# DDR3L.net
KiCad netlist of a schematic drawn in Altium Designer
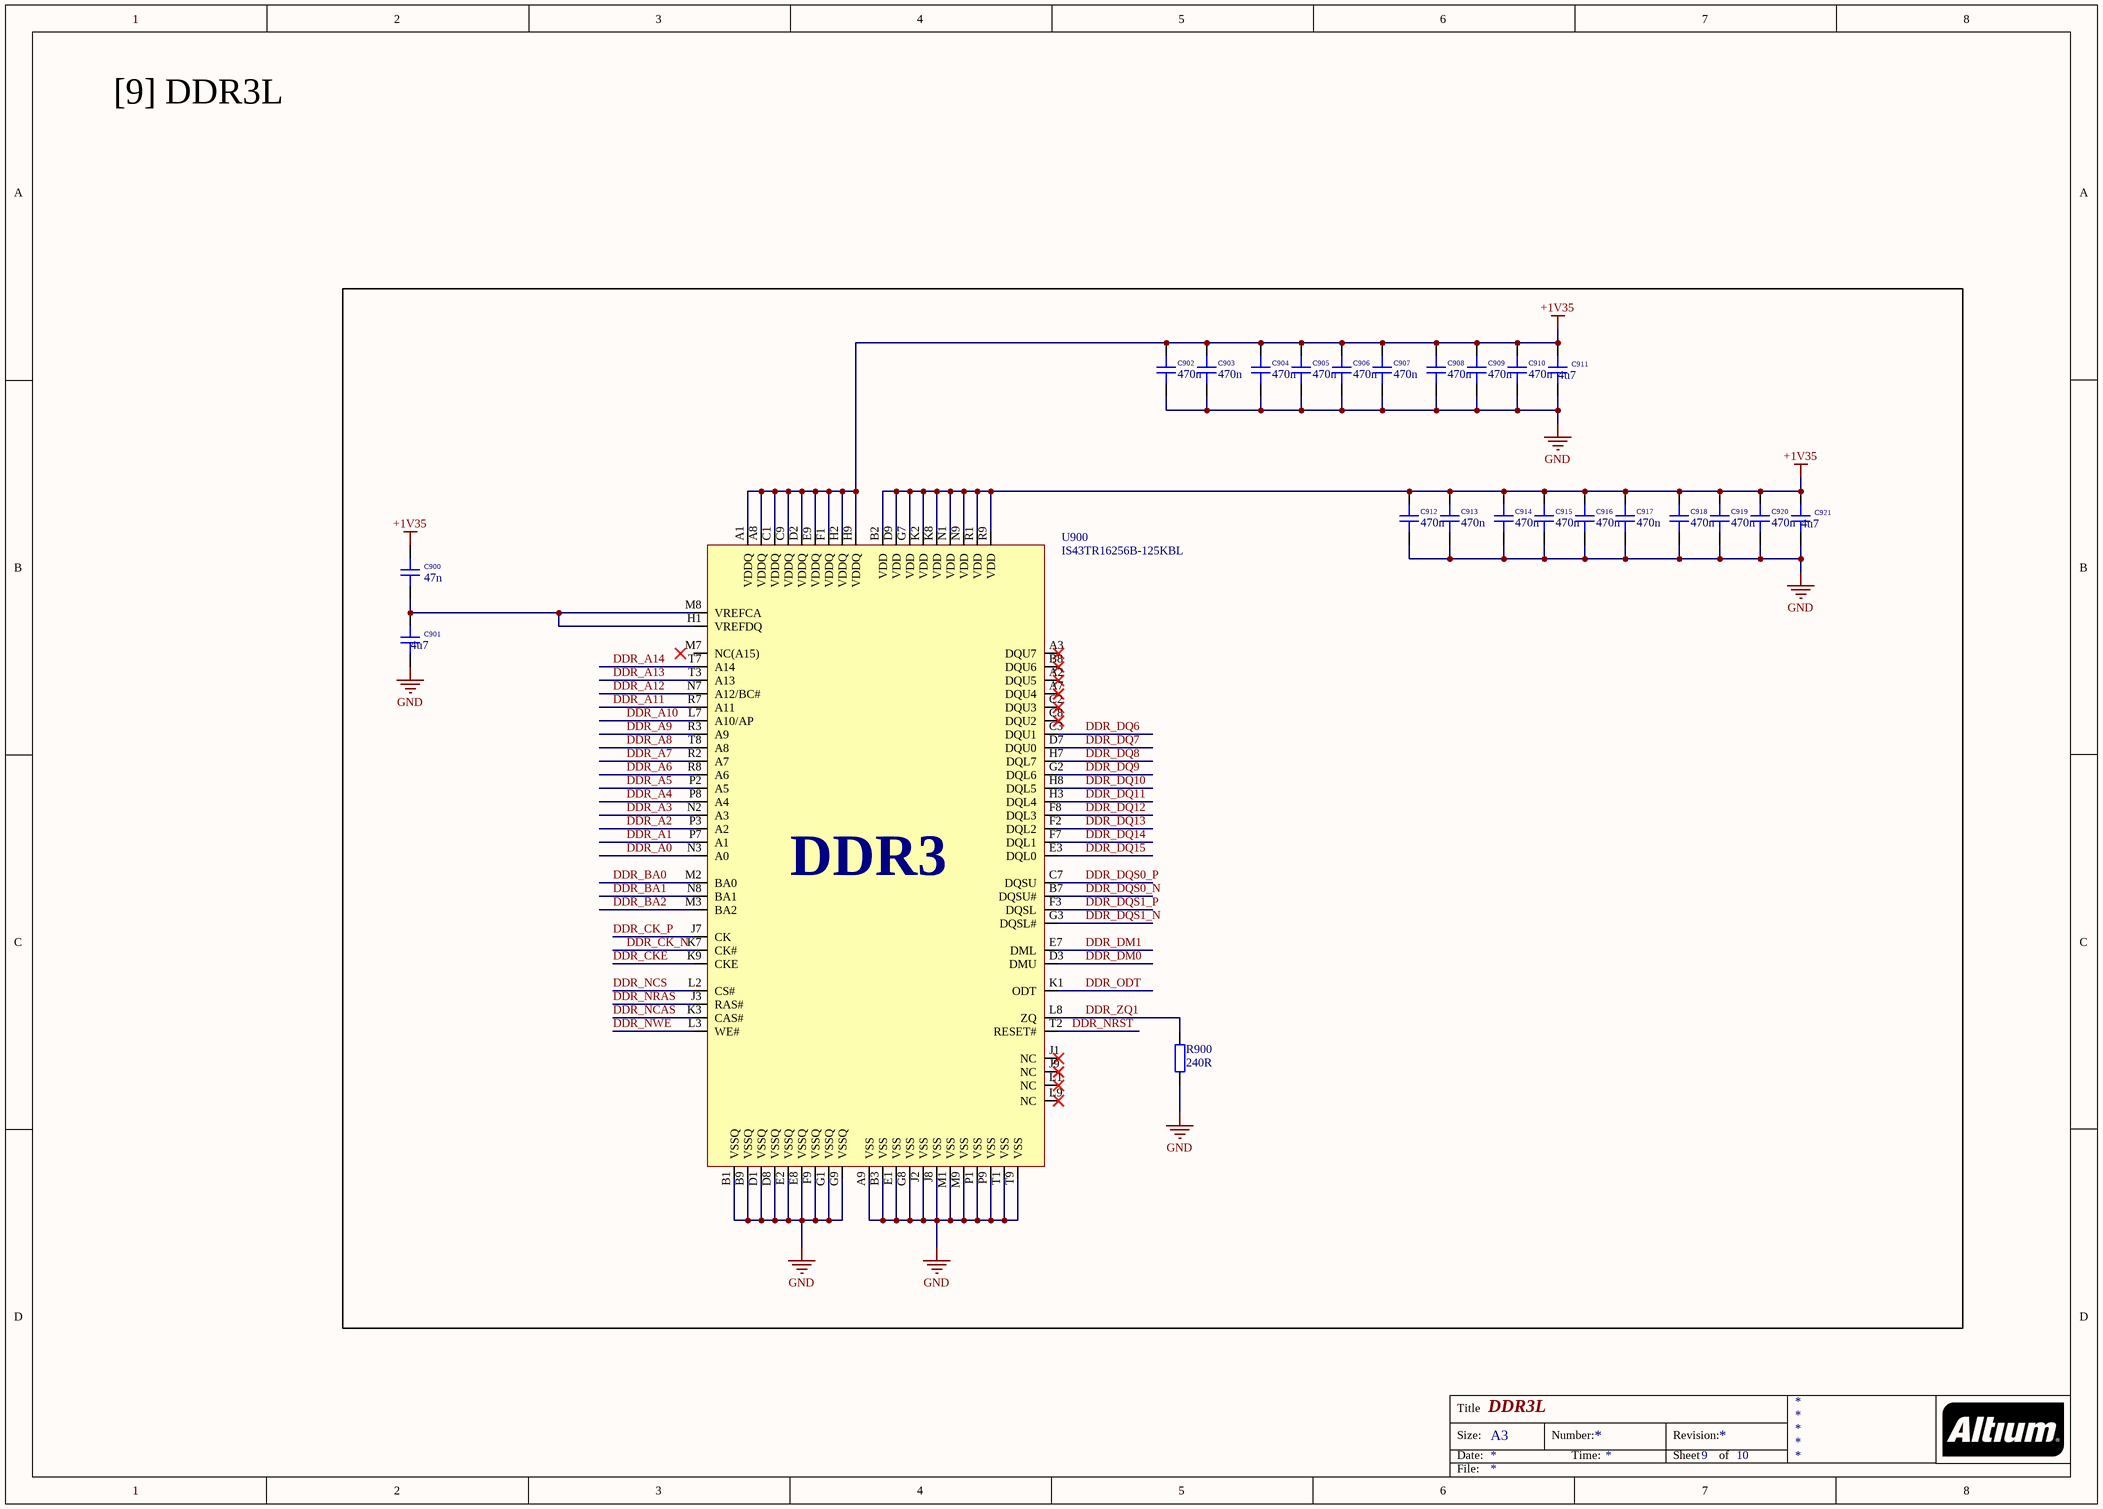
[diagram p0: DDR3L.SchDoc]

(export (version "E")
  (design (tool "Eeschema 10.0.6"))
  (components
    (comp (ref "C900")
      (value "47n")
      (footprint "CAP_1210")
      (description "Capacitor SMD 1210")
      (libsource (lib "Schematic-Lib-PhilsLab") (part "CAP_1210"))
    )
    (comp (ref "C901")
      (value "4u7")
      (footprint "CAP_1210")
      (description "Capacitor SMD 1210")
      (libsource (lib "Schematic-Lib-PhilsLab") (part "CAP_1210"))
    )
    (comp (ref "C902")
      (value "470n")
      (footprint "CAP_1210")
      (description "Capacitor SMD 1210")
      (libsource (lib "Schematic-Lib-PhilsLab") (part "CAP_1210"))
    )
    (comp (ref "C903")
      (value "470n")
      (footprint "CAP_1210")
      (description "Capacitor SMD 1210")
      (libsource (lib "Schematic-Lib-PhilsLab") (part "CAP_1210"))
    )
    (comp (ref "C904")
      (value "470n")
      (footprint "CAP_1210")
      (description "Capacitor SMD 1210")
      (libsource (lib "Schematic-Lib-PhilsLab") (part "CAP_1210"))
    )
    (comp (ref "C905")
      (value "470n")
      (footprint "CAP_1210")
      (description "Capacitor SMD 1210")
      (libsource (lib "Schematic-Lib-PhilsLab") (part "CAP_1210"))
    )
    (comp (ref "C906")
      (value "470n")
      (footprint "CAP_1210")
      (description "Capacitor SMD 1210")
      (libsource (lib "Schematic-Lib-PhilsLab") (part "CAP_1210"))
    )
    (comp (ref "C907")
      (value "470n")
      (footprint "CAP_1210")
      (description "Capacitor SMD 1210")
      (libsource (lib "Schematic-Lib-PhilsLab") (part "CAP_1210"))
    )
    (comp (ref "C908")
      (value "470n")
      (footprint "CAP_1210")
      (description "Capacitor SMD 1210")
      (libsource (lib "Schematic-Lib-PhilsLab") (part "CAP_1210"))
    )
    (comp (ref "C909")
      (value "470n")
      (footprint "CAP_1210")
      (description "Capacitor SMD 1210")
      (libsource (lib "Schematic-Lib-PhilsLab") (part "CAP_1210"))
    )
    (comp (ref "C910")
      (value "470n")
      (footprint "CAP_1210")
      (description "Capacitor SMD 1210")
      (libsource (lib "Schematic-Lib-PhilsLab") (part "CAP_1210"))
    )
    (comp (ref "C911")
      (value "4u7")
      (footprint "CAP_1210")
      (description "Capacitor SMD 1210")
      (libsource (lib "Schematic-Lib-PhilsLab") (part "CAP_1210"))
    )
    (comp (ref "C912")
      (value "470n")
      (footprint "CAP_1210")
      (description "Capacitor SMD 1210")
      (libsource (lib "Schematic-Lib-PhilsLab") (part "CAP_1210"))
    )
    (comp (ref "C913")
      (value "470n")
      (footprint "CAP_1210")
      (description "Capacitor SMD 1210")
      (libsource (lib "Schematic-Lib-PhilsLab") (part "CAP_1210"))
    )
    (comp (ref "C914")
      (value "470n")
      (footprint "CAP_1210")
      (description "Capacitor SMD 1210")
      (libsource (lib "Schematic-Lib-PhilsLab") (part "CAP_1210"))
    )
    (comp (ref "C915")
      (value "470n")
      (footprint "CAP_1210")
      (description "Capacitor SMD 1210")
      (libsource (lib "Schematic-Lib-PhilsLab") (part "CAP_1210"))
    )
    (comp (ref "C916")
      (value "470n")
      (footprint "CAP_1210")
      (description "Capacitor SMD 1210")
      (libsource (lib "Schematic-Lib-PhilsLab") (part "CAP_1210"))
    )
    (comp (ref "C917")
      (value "470n")
      (footprint "CAP_1210")
      (description "Capacitor SMD 1210")
      (libsource (lib "Schematic-Lib-PhilsLab") (part "CAP_1210"))
    )
    (comp (ref "C918")
      (value "470n")
      (footprint "CAP_1210")
      (description "Capacitor SMD 1210")
      (libsource (lib "Schematic-Lib-PhilsLab") (part "CAP_1210"))
    )
    (comp (ref "C919")
      (value "470n")
      (footprint "CAP_1210")
      (description "Capacitor SMD 1210")
      (libsource (lib "Schematic-Lib-PhilsLab") (part "CAP_1210"))
    )
    (comp (ref "C920")
      (value "470n")
      (footprint "CAP_1210")
      (description "Capacitor SMD 1210")
      (libsource (lib "Schematic-Lib-PhilsLab") (part "CAP_1210"))
    )
    (comp (ref "C921")
      (value "4u7")
      (footprint "CAP_1210")
      (description "Capacitor SMD 1210")
      (libsource (lib "Schematic-Lib-PhilsLab") (part "CAP_1210"))
    )
    (comp (ref "R900")
      (value "240R")
      (footprint "RES_0402")
      (description "Resistor SMD 0402")
      (libsource (lib "Schematic-Lib-PhilsLab") (part "RES_0402"))
    )
    (comp (ref "U900")
      (value "IS43TR16256B-125KBL")
      (footprint "BGA96C80P9X16_900X1300X120")
      (description "DRAM 4GBit, 1.5V, DDR3, 256Mx16, 1600MT/s @ 11-11-11, 96 ball BGA (9mm x13mm) RoHS")
      (fields (field (name "MANUFACTURER") "ISSI"))
      (libsource (lib "Schematic-Lib-PhilsLab") (part "IS43TR16256B-125KBL"))
    )
  )
  (nets
    (net (code "1") (name "+1V35") (class "Default")
      (node (ref "C900") (pin "2") (pinfunction "2_2") (pintype "passive"))
      (node (ref "C902") (pin "2") (pinfunction "2_2") (pintype "passive"))
      (node (ref "C903") (pin "2") (pinfunction "2_2") (pintype "passive"))
      (node (ref "C904") (pin "2") (pinfunction "2_2") (pintype "passive"))
      (node (ref "C905") (pin "2") (pinfunction "2_2") (pintype "passive"))
      (node (ref "C906") (pin "2") (pinfunction "2_2") (pintype "passive"))
      (node (ref "C907") (pin "2") (pinfunction "2_2") (pintype "passive"))
      (node (ref "C908") (pin "2") (pinfunction "2_2") (pintype "passive"))
      (node (ref "C909") (pin "2") (pinfunction "2_2") (pintype "passive"))
      (node (ref "C910") (pin "2") (pinfunction "2_2") (pintype "passive"))
      (node (ref "C911") (pin "2") (pinfunction "2_2") (pintype "passive"))
      (node (ref "C912") (pin "2") (pinfunction "2_2") (pintype "passive"))
      (node (ref "C913") (pin "2") (pinfunction "2_2") (pintype "passive"))
      (node (ref "C914") (pin "2") (pinfunction "2_2") (pintype "passive"))
      (node (ref "C915") (pin "2") (pinfunction "2_2") (pintype "passive"))
      (node (ref "C916") (pin "2") (pinfunction "2_2") (pintype "passive"))
      (node (ref "C917") (pin "2") (pinfunction "2_2") (pintype "passive"))
      (node (ref "C918") (pin "2") (pinfunction "2_2") (pintype "passive"))
      (node (ref "C919") (pin "2") (pinfunction "2_2") (pintype "passive"))
      (node (ref "C920") (pin "2") (pinfunction "2_2") (pintype "passive"))
      (node (ref "C921") (pin "2") (pinfunction "2_2") (pintype "passive"))
      (node (ref "U900") (pin "A1") (pinfunction "VDDQ_A1") (pintype "passive"))
      (node (ref "U900") (pin "A8") (pinfunction "VDDQ_A8") (pintype "passive"))
      (node (ref "U900") (pin "B2") (pinfunction "VDD_B2") (pintype "passive"))
      (node (ref "U900") (pin "C1") (pinfunction "VDDQ_C1") (pintype "passive"))
      (node (ref "U900") (pin "C9") (pinfunction "VDDQ_C9") (pintype "passive"))
      (node (ref "U900") (pin "D2") (pinfunction "VDDQ_D2") (pintype "passive"))
      (node (ref "U900") (pin "D9") (pinfunction "VDD_D9") (pintype "passive"))
      (node (ref "U900") (pin "E9") (pinfunction "VDDQ_E9") (pintype "passive"))
      (node (ref "U900") (pin "F1") (pinfunction "VDDQ_F1") (pintype "passive"))
      (node (ref "U900") (pin "G7") (pinfunction "VDD_G7") (pintype "passive"))
      (node (ref "U900") (pin "H2") (pinfunction "VDDQ_H2") (pintype "passive"))
      (node (ref "U900") (pin "H9") (pinfunction "VDDQ_H9") (pintype "passive"))
      (node (ref "U900") (pin "K2") (pinfunction "VDD_K2") (pintype "passive"))
      (node (ref "U900") (pin "K8") (pinfunction "VDD_K8") (pintype "passive"))
      (node (ref "U900") (pin "N1") (pinfunction "VDD_N1") (pintype "passive"))
      (node (ref "U900") (pin "N9") (pinfunction "VDD_N9") (pintype "passive"))
      (node (ref "U900") (pin "R1") (pinfunction "VDD_R1") (pintype "passive"))
      (node (ref "U900") (pin "R9") (pinfunction "VDD_R9") (pintype "passive"))
    )
    (net (code "2") (name "/DDR_A0") (class "Default")
      (node (ref "U900") (pin "N3") (pinfunction "A0_N3") (pintype "passive"))
    )
    (net (code "3") (name "/DDR_A1") (class "Default")
      (node (ref "U900") (pin "P7") (pinfunction "A1_P7") (pintype "passive"))
    )
    (net (code "4") (name "/DDR_A2") (class "Default")
      (node (ref "U900") (pin "P3") (pinfunction "A2_P3") (pintype "passive"))
    )
    (net (code "5") (name "/DDR_A3") (class "Default")
      (node (ref "U900") (pin "N2") (pinfunction "A3_N2") (pintype "passive"))
    )
    (net (code "6") (name "/DDR_A4") (class "Default")
      (node (ref "U900") (pin "P8") (pinfunction "A4_P8") (pintype "passive"))
    )
    (net (code "7") (name "/DDR_A5") (class "Default")
      (node (ref "U900") (pin "P2") (pinfunction "A5_P2") (pintype "passive"))
    )
    (net (code "8") (name "/DDR_A6") (class "Default")
      (node (ref "U900") (pin "R8") (pinfunction "A6_R8") (pintype "passive"))
    )
    (net (code "9") (name "/DDR_A7") (class "Default")
      (node (ref "U900") (pin "R2") (pinfunction "A7_R2") (pintype "passive"))
    )
    (net (code "10") (name "/DDR_A8") (class "Default")
      (node (ref "U900") (pin "T8") (pinfunction "A8_T8") (pintype "passive"))
    )
    (net (code "11") (name "/DDR_A9") (class "Default")
      (node (ref "U900") (pin "R3") (pinfunction "A9_R3") (pintype "passive"))
    )
    (net (code "12") (name "/DDR_A10") (class "Default")
      (node (ref "U900") (pin "L7") (pinfunction "A10/AP_L7") (pintype "passive"))
    )
    (net (code "13") (name "/DDR_A11") (class "Default")
      (node (ref "U900") (pin "R7") (pinfunction "A11_R7") (pintype "passive"))
    )
    (net (code "14") (name "/DDR_A12") (class "Default")
      (node (ref "U900") (pin "N7") (pinfunction "A12/BC#_N7") (pintype "passive"))
    )
    (net (code "15") (name "/DDR_A13") (class "Default")
      (node (ref "U900") (pin "T3") (pinfunction "A13_T3") (pintype "passive"))
    )
    (net (code "16") (name "/DDR_A14") (class "Default")
      (node (ref "U900") (pin "T7") (pinfunction "A14_T7") (pintype "passive"))
    )
    (net (code "17") (name "/DDR_BA0") (class "Default")
      (node (ref "U900") (pin "M2") (pinfunction "BA0_M2") (pintype "passive"))
    )
    (net (code "18") (name "/DDR_BA1") (class "Default")
      (node (ref "U900") (pin "N8") (pinfunction "BA1_N8") (pintype "passive"))
    )
    (net (code "19") (name "/DDR_BA2") (class "Default")
      (node (ref "U900") (pin "M3") (pinfunction "BA2_M3") (pintype "passive"))
    )
    (net (code "20") (name "/DDR_CKE") (class "Default")
      (node (ref "U900") (pin "K9") (pinfunction "CKE_K9") (pintype "passive"))
    )
    (net (code "21") (name "/DDR_CK_N") (class "Default")
      (node (ref "U900") (pin "K7") (pinfunction "CK#_K7") (pintype "passive"))
    )
    (net (code "22") (name "/DDR_CK_P") (class "Default")
      (node (ref "U900") (pin "J7") (pinfunction "CK_J7") (pintype "passive"))
    )
    (net (code "23") (name "/DDR_DM0") (class "Default")
      (node (ref "U900") (pin "D3") (pinfunction "DMU_D3") (pintype "passive"))
    )
    (net (code "24") (name "/DDR_DM1") (class "Default")
      (node (ref "U900") (pin "E7") (pinfunction "DML_E7") (pintype "passive"))
    )
    (net (code "25") (name "/DDR_DQ6") (class "Default")
      (node (ref "U900") (pin "C3") (pinfunction "DQU1_C3") (pintype "passive"))
    )
    (net (code "26") (name "/DDR_DQ7") (class "Default")
      (node (ref "U900") (pin "D7") (pinfunction "DQU0_D7") (pintype "passive"))
    )
    (net (code "27") (name "/DDR_DQ8") (class "Default")
      (node (ref "U900") (pin "H7") (pinfunction "DQL7_H7") (pintype "passive"))
    )
    (net (code "28") (name "/DDR_DQ9") (class "Default")
      (node (ref "U900") (pin "G2") (pinfunction "DQL6_G2") (pintype "passive"))
    )
    (net (code "29") (name "/DDR_DQ10") (class "Default")
      (node (ref "U900") (pin "H8") (pinfunction "DQL5_H8") (pintype "passive"))
    )
    (net (code "30") (name "/DDR_DQ11") (class "Default")
      (node (ref "U900") (pin "H3") (pinfunction "DQL4_H3") (pintype "passive"))
    )
    (net (code "31") (name "/DDR_DQ12") (class "Default")
      (node (ref "U900") (pin "F8") (pinfunction "DQL3_F8") (pintype "passive"))
    )
    (net (code "32") (name "/DDR_DQ13") (class "Default")
      (node (ref "U900") (pin "F2") (pinfunction "DQL2_F2") (pintype "passive"))
    )
    (net (code "33") (name "/DDR_DQ14") (class "Default")
      (node (ref "U900") (pin "F7") (pinfunction "DQL1_F7") (pintype "passive"))
    )
    (net (code "34") (name "/DDR_DQ15") (class "Default")
      (node (ref "U900") (pin "E3") (pinfunction "DQL0_E3") (pintype "passive"))
    )
    (net (code "35") (name "/DDR_DQS0_N") (class "Default")
      (node (ref "U900") (pin "B7") (pinfunction "DQSU#_B7") (pintype "passive"))
    )
    (net (code "36") (name "/DDR_DQS0_P") (class "Default")
      (node (ref "U900") (pin "C7") (pinfunction "DQSU_C7") (pintype "passive"))
    )
    (net (code "37") (name "/DDR_DQS1_N") (class "Default")
      (node (ref "U900") (pin "G3") (pinfunction "DQSL#_G3") (pintype "passive"))
    )
    (net (code "38") (name "/DDR_DQS1_P") (class "Default")
      (node (ref "U900") (pin "F3") (pinfunction "DQSL_F3") (pintype "passive"))
    )
    (net (code "39") (name "/DDR_NCAS") (class "Default")
      (node (ref "U900") (pin "K3") (pinfunction "CAS#_K3") (pintype "passive"))
    )
    (net (code "40") (name "/DDR_NCS") (class "Default")
      (node (ref "U900") (pin "L2") (pinfunction "CS#_L2") (pintype "passive"))
    )
    (net (code "41") (name "/DDR_NRAS") (class "Default")
      (node (ref "U900") (pin "J3") (pinfunction "RAS#_J3") (pintype "passive"))
    )
    (net (code "42") (name "/DDR_NRST") (class "Default")
      (node (ref "U900") (pin "T2") (pinfunction "RESET#_T2") (pintype "passive"))
    )
    (net (code "43") (name "/DDR_NWE") (class "Default")
      (node (ref "U900") (pin "L3") (pinfunction "WE#_L3") (pintype "passive"))
    )
    (net (code "44") (name "/DDR_ODT") (class "Default")
      (node (ref "U900") (pin "K1") (pinfunction "ODT_K1") (pintype "passive"))
    )
    (net (code "45") (name "/DDR_ZQ1") (class "Default")
      (node (ref "R900") (pin "1") (pinfunction "1_1") (pintype "passive"))
      (node (ref "U900") (pin "L8") (pinfunction "ZQ_L8") (pintype "passive"))
    )
    (net (code "46") (name "GND") (class "Default")
      (node (ref "C901") (pin "1") (pinfunction "1_1") (pintype "passive"))
      (node (ref "C902") (pin "1") (pinfunction "1_1") (pintype "passive"))
      (node (ref "C903") (pin "1") (pinfunction "1_1") (pintype "passive"))
      (node (ref "C904") (pin "1") (pinfunction "1_1") (pintype "passive"))
      (node (ref "C905") (pin "1") (pinfunction "1_1") (pintype "passive"))
      (node (ref "C906") (pin "1") (pinfunction "1_1") (pintype "passive"))
      (node (ref "C907") (pin "1") (pinfunction "1_1") (pintype "passive"))
      (node (ref "C908") (pin "1") (pinfunction "1_1") (pintype "passive"))
      (node (ref "C909") (pin "1") (pinfunction "1_1") (pintype "passive"))
      (node (ref "C910") (pin "1") (pinfunction "1_1") (pintype "passive"))
      (node (ref "C911") (pin "1") (pinfunction "1_1") (pintype "passive"))
      (node (ref "C912") (pin "1") (pinfunction "1_1") (pintype "passive"))
      (node (ref "C913") (pin "1") (pinfunction "1_1") (pintype "passive"))
      (node (ref "C914") (pin "1") (pinfunction "1_1") (pintype "passive"))
      (node (ref "C915") (pin "1") (pinfunction "1_1") (pintype "passive"))
      (node (ref "C916") (pin "1") (pinfunction "1_1") (pintype "passive"))
      (node (ref "C917") (pin "1") (pinfunction "1_1") (pintype "passive"))
      (node (ref "C918") (pin "1") (pinfunction "1_1") (pintype "passive"))
      (node (ref "C919") (pin "1") (pinfunction "1_1") (pintype "passive"))
      (node (ref "C920") (pin "1") (pinfunction "1_1") (pintype "passive"))
      (node (ref "C921") (pin "1") (pinfunction "1_1") (pintype "passive"))
      (node (ref "R900") (pin "2") (pinfunction "2_2") (pintype "passive"))
      (node (ref "U900") (pin "A9") (pinfunction "VSS_A9") (pintype "passive"))
      (node (ref "U900") (pin "B1") (pinfunction "VSSQ_B1") (pintype "passive"))
      (node (ref "U900") (pin "B3") (pinfunction "VSS_B3") (pintype "passive"))
      (node (ref "U900") (pin "B9") (pinfunction "VSSQ_B9") (pintype "passive"))
      (node (ref "U900") (pin "D1") (pinfunction "VSSQ_D1") (pintype "passive"))
      (node (ref "U900") (pin "D8") (pinfunction "VSSQ_D8") (pintype "passive"))
      (node (ref "U900") (pin "E1") (pinfunction "VSS_E1") (pintype "passive"))
      (node (ref "U900") (pin "E2") (pinfunction "VSSQ_E2") (pintype "passive"))
      (node (ref "U900") (pin "E8") (pinfunction "VSSQ_E8") (pintype "passive"))
      (node (ref "U900") (pin "F9") (pinfunction "VSSQ_F9") (pintype "passive"))
      (node (ref "U900") (pin "G1") (pinfunction "VSSQ_G1") (pintype "passive"))
      (node (ref "U900") (pin "G8") (pinfunction "VSS_G8") (pintype "passive"))
      (node (ref "U900") (pin "G9") (pinfunction "VSSQ_G9") (pintype "passive"))
      (node (ref "U900") (pin "J2") (pinfunction "VSS_J2") (pintype "passive"))
      (node (ref "U900") (pin "J8") (pinfunction "VSS_J8") (pintype "passive"))
      (node (ref "U900") (pin "M1") (pinfunction "VSS_M1") (pintype "passive"))
      (node (ref "U900") (pin "M9") (pinfunction "VSS_M9") (pintype "passive"))
      (node (ref "U900") (pin "P1") (pinfunction "VSS_P1") (pintype "passive"))
      (node (ref "U900") (pin "P9") (pinfunction "VSS_P9") (pintype "passive"))
      (node (ref "U900") (pin "T1") (pinfunction "VSS_T1") (pintype "passive"))
      (node (ref "U900") (pin "T9") (pinfunction "VSS_T9") (pintype "passive"))
    )
    (net (code "47") (name "Net-(U900-VREFCA)") (class "Default")
      (node (ref "C900") (pin "1") (pinfunction "1_1") (pintype "passive"))
      (node (ref "C901") (pin "2") (pinfunction "2_2") (pintype "passive"))
      (node (ref "U900") (pin "H1") (pinfunction "VREFDQ_H1") (pintype "passive"))
      (node (ref "U900") (pin "M8") (pinfunction "VREFCA_M8") (pintype "passive"))
    )
    (net (code "48") (name "unconnected-(U900-DQU2-PadC8)") (class "Default")
      (node (ref "U900") (pin "C8") (pinfunction "DQU2_C8") (pintype "passive+no_connect"))
    )
    (net (code "49") (name "unconnected-(U900-DQU3-PadC2)") (class "Default")
      (node (ref "U900") (pin "C2") (pinfunction "DQU3_C2") (pintype "passive+no_connect"))
    )
    (net (code "50") (name "unconnected-(U900-DQU4-PadA7)") (class "Default")
      (node (ref "U900") (pin "A7") (pinfunction "DQU4_A7") (pintype "passive+no_connect"))
    )
    (net (code "51") (name "unconnected-(U900-DQU5-PadA2)") (class "Default")
      (node (ref "U900") (pin "A2") (pinfunction "DQU5_A2") (pintype "passive+no_connect"))
    )
    (net (code "52") (name "unconnected-(U900-DQU6-PadB8)") (class "Default")
      (node (ref "U900") (pin "B8") (pinfunction "DQU6_B8") (pintype "passive+no_connect"))
    )
    (net (code "53") (name "unconnected-(U900-DQU7-PadA3)") (class "Default")
      (node (ref "U900") (pin "A3") (pinfunction "DQU7_A3") (pintype "passive+no_connect"))
    )
    (net (code "54") (name "unconnected-(U900-NC(A15)-PadM7)") (class "Default")
      (node (ref "U900") (pin "M7") (pinfunction "NC(A15)_M7") (pintype "passive"))
    )
    (net (code "55") (name "unconnected-(U900-NC-PadJ1)") (class "Default")
      (node (ref "U900") (pin "J1") (pinfunction "NC_J1") (pintype "passive+no_connect"))
    )
    (net (code "56") (name "unconnected-(U900-NC-PadJ9)") (class "Default")
      (node (ref "U900") (pin "J9") (pinfunction "NC_J9") (pintype "passive+no_connect"))
    )
    (net (code "57") (name "unconnected-(U900-NC-PadL1)") (class "Default")
      (node (ref "U900") (pin "L1") (pinfunction "NC_L1") (pintype "passive+no_connect"))
    )
    (net (code "58") (name "unconnected-(U900-NC-PadL9)") (class "Default")
      (node (ref "U900") (pin "L9") (pinfunction "NC_L9") (pintype "passive+no_connect"))
    )
  )
)
